# DisplayArrayPlus.net
KiCad netlist of a schematic drawn in EAGLE
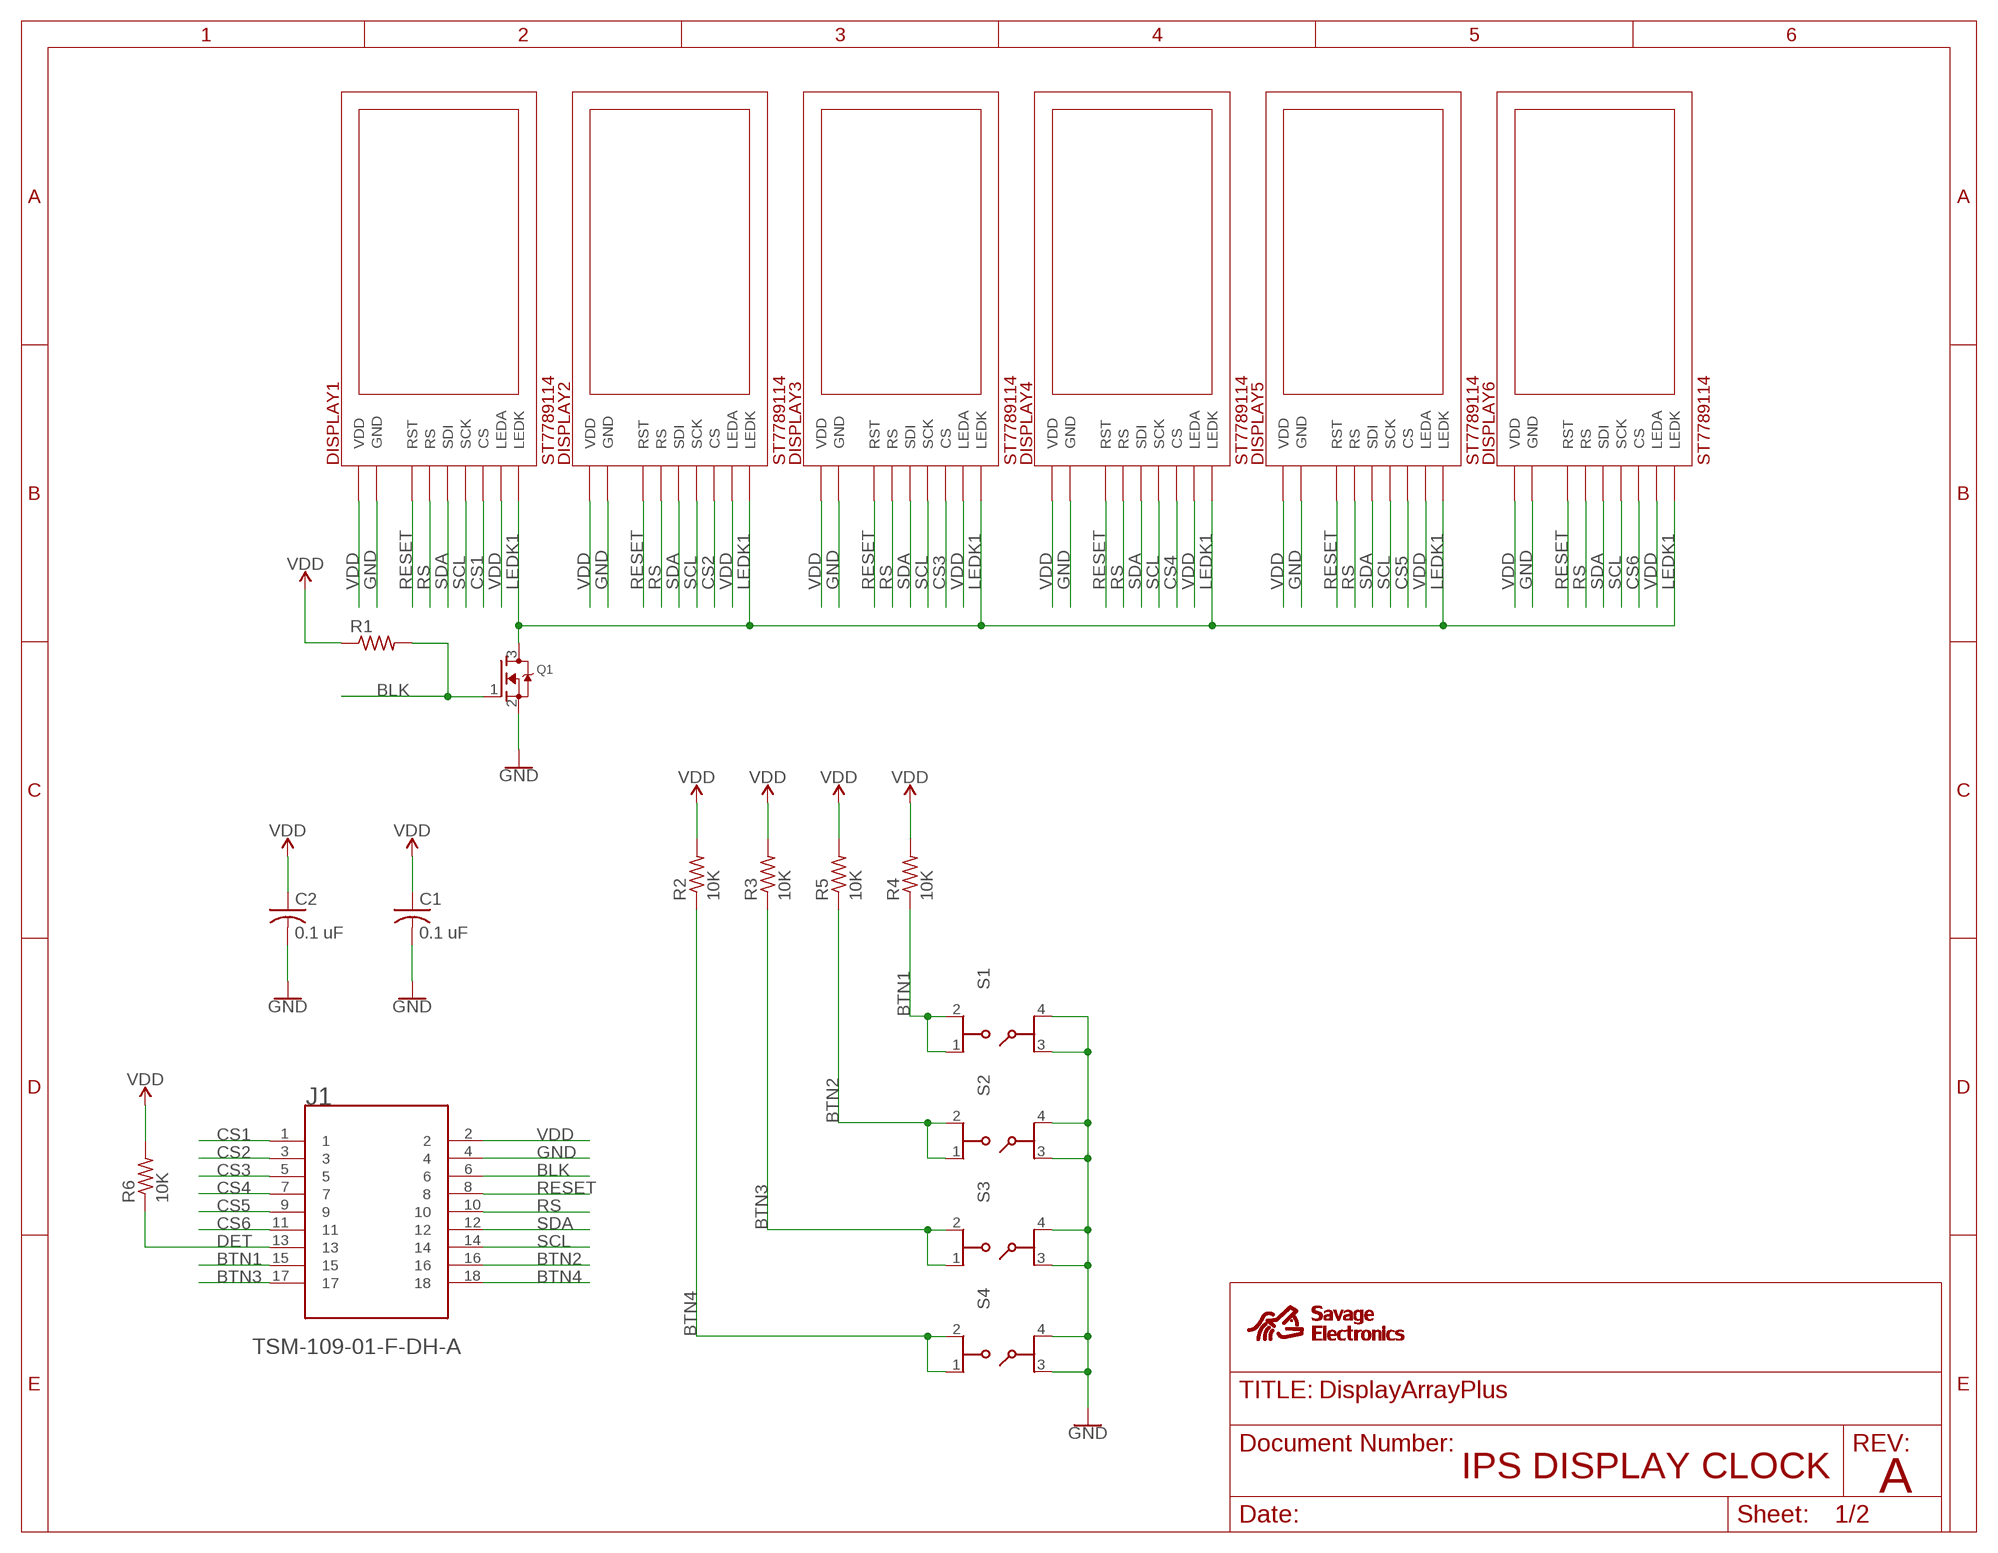
[diagram p0: schematic, sheet 1]

(export (version "E")
  (design (tool "Eeschema 10.0.6"))
  (components
    (comp (ref "C1")
      (value "0.1 uF")
      (footprint "eagle-import:C0603")
      (libsource (lib "eagle-import") (part "C-USC0603"))
    )
    (comp (ref "C2")
      (value "0.1 uF")
      (footprint "eagle-import:C0603")
      (libsource (lib "eagle-import") (part "C-USC0603"))
    )
    (comp (ref "DISPLAY1")
      (value "ST7789114")
      (footprint "eagle-import:IPSLCD114")
      (libsource (lib "eagle-import") (part "ST7789114"))
    )
    (comp (ref "DISPLAY2")
      (value "ST7789114")
      (footprint "eagle-import:IPSLCD114")
      (libsource (lib "eagle-import") (part "ST7789114"))
    )
    (comp (ref "DISPLAY3")
      (value "ST7789114")
      (footprint "eagle-import:IPSLCD114")
      (libsource (lib "eagle-import") (part "ST7789114"))
    )
    (comp (ref "DISPLAY4")
      (value "ST7789114")
      (footprint "eagle-import:IPSLCD114")
      (libsource (lib "eagle-import") (part "ST7789114"))
    )
    (comp (ref "DISPLAY5")
      (value "ST7789114")
      (footprint "eagle-import:IPSLCD114")
      (libsource (lib "eagle-import") (part "ST7789114"))
    )
    (comp (ref "DISPLAY6")
      (value "ST7789114")
      (footprint "eagle-import:IPSLCD114")
      (libsource (lib "eagle-import") (part "ST7789114"))
    )
    (comp (ref "J1")
      (value "TSM-109-01-F-DH-A")
      (footprint "eagle-import:SAMTEC-TSM-109-02-X-DH-A")
      (libsource (lib "eagle-import") (part "SAMTEC-TSM-109-02-X-DH-AJ"))
    )
    (comp (ref "Q1")
      (value "MOSFET-NREFLOW")
      (footprint "eagle-import:SOT23")
      (libsource (lib "eagle-import") (part "MOSFET-NREFLOW"))
    )
    (comp (ref "R1")
      (value "R-US_R0805")
      (footprint "eagle-import:R0805")
      (libsource (lib "eagle-import") (part "R-US_R0805"))
    )
    (comp (ref "R2")
      (value "10K")
      (footprint "eagle-import:R0805")
      (libsource (lib "eagle-import") (part "R-US_R0805"))
    )
    (comp (ref "R3")
      (value "10K")
      (footprint "eagle-import:R0805")
      (libsource (lib "eagle-import") (part "R-US_R0805"))
    )
    (comp (ref "R4")
      (value "10K")
      (footprint "eagle-import:R0805")
      (libsource (lib "eagle-import") (part "R-US_R0805"))
    )
    (comp (ref "R5")
      (value "10K")
      (footprint "eagle-import:R0805")
      (libsource (lib "eagle-import") (part "R-US_R0805"))
    )
    (comp (ref "R6")
      (value "10K")
      (footprint "eagle-import:R0805")
      (libsource (lib "eagle-import") (part "R-US_R0805"))
    )
    (comp (ref "S1")
      (value "434123025826")
      (footprint "eagle-import:434123025826")
      (libsource (lib "eagle-import") (part "434123025826"))
    )
    (comp (ref "S2")
      (value "434123025826")
      (footprint "eagle-import:434123025826")
      (libsource (lib "eagle-import") (part "434123025826"))
    )
    (comp (ref "S3")
      (value "434123025826")
      (footprint "eagle-import:434123025826")
      (libsource (lib "eagle-import") (part "434123025826"))
    )
    (comp (ref "S4")
      (value "434123025826")
      (footprint "eagle-import:434123025826")
      (libsource (lib "eagle-import") (part "434123025826"))
    )
    (comp (ref "U$3")
      (value "SE_SMALL_SILK")
      (footprint "eagle-import:SE_SMALL_SILK")
      (libsource (lib "eagle-import") (part "SE_SMALL_SILK"))
    )
  )
  (nets
    (net (code "1") (name "BLK") (class "Default")
      (node (ref "J1") (pin "6") (pinfunction "6_6") (pintype "passive"))
      (node (ref "Q1") (pin "1") (pinfunction "G_1") (pintype "bidirectional"))
      (node (ref "R1") (pin "2") (pinfunction "2_2") (pintype "passive"))
    )
    (net (code "2") (name "BTN1") (class "Default")
      (node (ref "J1") (pin "15") (pinfunction "15_15") (pintype "passive"))
      (node (ref "R4") (pin "1") (pinfunction "1_1") (pintype "passive"))
      (node (ref "S1") (pin "1") (pinfunction "1_1") (pintype "passive"))
      (node (ref "S1") (pin "2") (pinfunction "2_2") (pintype "passive"))
    )
    (net (code "3") (name "BTN2") (class "Default")
      (node (ref "J1") (pin "16") (pinfunction "16_16") (pintype "passive"))
      (node (ref "R5") (pin "1") (pinfunction "1_1") (pintype "passive"))
      (node (ref "S2") (pin "1") (pinfunction "1_1") (pintype "passive"))
      (node (ref "S2") (pin "2") (pinfunction "2_2") (pintype "passive"))
    )
    (net (code "4") (name "BTN3") (class "Default")
      (node (ref "J1") (pin "17") (pinfunction "17_17") (pintype "passive"))
      (node (ref "R3") (pin "1") (pinfunction "1_1") (pintype "passive"))
      (node (ref "S3") (pin "1") (pinfunction "1_1") (pintype "passive"))
      (node (ref "S3") (pin "2") (pinfunction "2_2") (pintype "passive"))
    )
    (net (code "5") (name "BTN4") (class "Default")
      (node (ref "J1") (pin "18") (pinfunction "18_18") (pintype "passive"))
      (node (ref "R2") (pin "1") (pinfunction "1_1") (pintype "passive"))
      (node (ref "S4") (pin "1") (pinfunction "1_1") (pintype "passive"))
      (node (ref "S4") (pin "2") (pinfunction "2_2") (pintype "passive"))
    )
    (net (code "6") (name "CS1") (class "Default")
      (node (ref "DISPLAY1") (pin "7") (pinfunction "CS_7") (pintype "bidirectional"))
      (node (ref "J1") (pin "1") (pinfunction "1_1") (pintype "passive"))
    )
    (net (code "7") (name "CS2") (class "Default")
      (node (ref "DISPLAY2") (pin "7") (pinfunction "CS_7") (pintype "bidirectional"))
      (node (ref "J1") (pin "3") (pinfunction "3_3") (pintype "passive"))
    )
    (net (code "8") (name "CS3") (class "Default")
      (node (ref "DISPLAY3") (pin "7") (pinfunction "CS_7") (pintype "bidirectional"))
      (node (ref "J1") (pin "5") (pinfunction "5_5") (pintype "passive"))
    )
    (net (code "9") (name "CS4") (class "Default")
      (node (ref "DISPLAY4") (pin "7") (pinfunction "CS_7") (pintype "bidirectional"))
      (node (ref "J1") (pin "7") (pinfunction "7_7") (pintype "passive"))
    )
    (net (code "10") (name "CS5") (class "Default")
      (node (ref "DISPLAY5") (pin "7") (pinfunction "CS_7") (pintype "bidirectional"))
      (node (ref "J1") (pin "9") (pinfunction "9_9") (pintype "passive"))
    )
    (net (code "11") (name "CS6") (class "Default")
      (node (ref "DISPLAY6") (pin "7") (pinfunction "CS_7") (pintype "bidirectional"))
      (node (ref "J1") (pin "11") (pinfunction "11_11") (pintype "passive"))
    )
    (net (code "12") (name "DET") (class "Default")
      (node (ref "J1") (pin "13") (pinfunction "13_13") (pintype "passive"))
      (node (ref "R6") (pin "1") (pinfunction "1_1") (pintype "passive"))
    )
    (net (code "13") (name "GND") (class "Default")
      (node (ref "C1") (pin "2") (pinfunction "2_2") (pintype "passive"))
      (node (ref "C2") (pin "2") (pinfunction "2_2") (pintype "passive"))
      (node (ref "DISPLAY1") (pin "13") (pinfunction "GND_13") (pintype "bidirectional"))
      (node (ref "DISPLAY1") (pin "8") (pinfunction "GND_8") (pintype "bidirectional"))
      (node (ref "DISPLAY2") (pin "13") (pinfunction "GND_13") (pintype "bidirectional"))
      (node (ref "DISPLAY2") (pin "8") (pinfunction "GND_8") (pintype "bidirectional"))
      (node (ref "DISPLAY3") (pin "13") (pinfunction "GND_13") (pintype "bidirectional"))
      (node (ref "DISPLAY3") (pin "8") (pinfunction "GND_8") (pintype "bidirectional"))
      (node (ref "DISPLAY4") (pin "13") (pinfunction "GND_13") (pintype "bidirectional"))
      (node (ref "DISPLAY4") (pin "8") (pinfunction "GND_8") (pintype "bidirectional"))
      (node (ref "DISPLAY5") (pin "13") (pinfunction "GND_13") (pintype "bidirectional"))
      (node (ref "DISPLAY5") (pin "8") (pinfunction "GND_8") (pintype "bidirectional"))
      (node (ref "DISPLAY6") (pin "13") (pinfunction "GND_13") (pintype "bidirectional"))
      (node (ref "DISPLAY6") (pin "8") (pinfunction "GND_8") (pintype "bidirectional"))
      (node (ref "J1") (pin "4") (pinfunction "4_4") (pintype "passive"))
      (node (ref "Q1") (pin "2") (pinfunction "S_2") (pintype "bidirectional"))
      (node (ref "S1") (pin "3") (pinfunction "3_3") (pintype "passive"))
      (node (ref "S1") (pin "4") (pinfunction "4_4") (pintype "passive"))
      (node (ref "S2") (pin "3") (pinfunction "3_3") (pintype "passive"))
      (node (ref "S2") (pin "4") (pinfunction "4_4") (pintype "passive"))
      (node (ref "S3") (pin "3") (pinfunction "3_3") (pintype "passive"))
      (node (ref "S3") (pin "4") (pinfunction "4_4") (pintype "passive"))
      (node (ref "S4") (pin "3") (pinfunction "3_3") (pintype "passive"))
      (node (ref "S4") (pin "4") (pinfunction "4_4") (pintype "passive"))
    )
    (net (code "14") (name "LEDK1") (class "Default")
      (node (ref "DISPLAY1") (pin "11") (pinfunction "LEDK_11") (pintype "bidirectional"))
      (node (ref "DISPLAY2") (pin "11") (pinfunction "LEDK_11") (pintype "bidirectional"))
      (node (ref "DISPLAY3") (pin "11") (pinfunction "LEDK_11") (pintype "bidirectional"))
      (node (ref "DISPLAY4") (pin "11") (pinfunction "LEDK_11") (pintype "bidirectional"))
      (node (ref "DISPLAY5") (pin "11") (pinfunction "LEDK_11") (pintype "bidirectional"))
      (node (ref "DISPLAY6") (pin "11") (pinfunction "LEDK_11") (pintype "bidirectional"))
      (node (ref "Q1") (pin "3") (pinfunction "D_3") (pintype "bidirectional"))
    )
    (net (code "15") (name "RESET") (class "Default")
      (node (ref "DISPLAY1") (pin "6") (pinfunction "RST_6") (pintype "bidirectional"))
      (node (ref "DISPLAY2") (pin "6") (pinfunction "RST_6") (pintype "bidirectional"))
      (node (ref "DISPLAY3") (pin "6") (pinfunction "RST_6") (pintype "bidirectional"))
      (node (ref "DISPLAY4") (pin "6") (pinfunction "RST_6") (pintype "bidirectional"))
      (node (ref "DISPLAY5") (pin "6") (pinfunction "RST_6") (pintype "bidirectional"))
      (node (ref "DISPLAY6") (pin "6") (pinfunction "RST_6") (pintype "bidirectional"))
      (node (ref "J1") (pin "8") (pinfunction "8_8") (pintype "passive"))
    )
    (net (code "16") (name "RS") (class "Default")
      (node (ref "DISPLAY1") (pin "5") (pinfunction "RS_5") (pintype "bidirectional"))
      (node (ref "DISPLAY2") (pin "5") (pinfunction "RS_5") (pintype "bidirectional"))
      (node (ref "DISPLAY3") (pin "5") (pinfunction "RS_5") (pintype "bidirectional"))
      (node (ref "DISPLAY4") (pin "5") (pinfunction "RS_5") (pintype "bidirectional"))
      (node (ref "DISPLAY5") (pin "5") (pinfunction "RS_5") (pintype "bidirectional"))
      (node (ref "DISPLAY6") (pin "5") (pinfunction "RS_5") (pintype "bidirectional"))
      (node (ref "J1") (pin "10") (pinfunction "10_10") (pintype "passive"))
    )
    (net (code "17") (name "SCL") (class "Default")
      (node (ref "DISPLAY1") (pin "4") (pinfunction "SCK_4") (pintype "bidirectional"))
      (node (ref "DISPLAY2") (pin "4") (pinfunction "SCK_4") (pintype "bidirectional"))
      (node (ref "DISPLAY3") (pin "4") (pinfunction "SCK_4") (pintype "bidirectional"))
      (node (ref "DISPLAY4") (pin "4") (pinfunction "SCK_4") (pintype "bidirectional"))
      (node (ref "DISPLAY5") (pin "4") (pinfunction "SCK_4") (pintype "bidirectional"))
      (node (ref "DISPLAY6") (pin "4") (pinfunction "SCK_4") (pintype "bidirectional"))
      (node (ref "J1") (pin "14") (pinfunction "14_14") (pintype "passive"))
    )
    (net (code "18") (name "SDA") (class "Default")
      (node (ref "DISPLAY1") (pin "3") (pinfunction "SDI_3") (pintype "bidirectional"))
      (node (ref "DISPLAY2") (pin "3") (pinfunction "SDI_3") (pintype "bidirectional"))
      (node (ref "DISPLAY3") (pin "3") (pinfunction "SDI_3") (pintype "bidirectional"))
      (node (ref "DISPLAY4") (pin "3") (pinfunction "SDI_3") (pintype "bidirectional"))
      (node (ref "DISPLAY5") (pin "3") (pinfunction "SDI_3") (pintype "bidirectional"))
      (node (ref "DISPLAY6") (pin "3") (pinfunction "SDI_3") (pintype "bidirectional"))
      (node (ref "J1") (pin "12") (pinfunction "12_12") (pintype "passive"))
    )
    (net (code "19") (name "VDD") (class "Default")
      (node (ref "C1") (pin "1") (pinfunction "1_1") (pintype "passive"))
      (node (ref "C2") (pin "1") (pinfunction "1_1") (pintype "passive"))
      (node (ref "DISPLAY1") (pin "10") (pinfunction "VDD_10") (pintype "bidirectional"))
      (node (ref "DISPLAY1") (pin "12") (pinfunction "LEDA_12") (pintype "bidirectional"))
      (node (ref "DISPLAY2") (pin "10") (pinfunction "VDD_10") (pintype "bidirectional"))
      (node (ref "DISPLAY2") (pin "12") (pinfunction "LEDA_12") (pintype "bidirectional"))
      (node (ref "DISPLAY3") (pin "10") (pinfunction "VDD_10") (pintype "bidirectional"))
      (node (ref "DISPLAY3") (pin "12") (pinfunction "LEDA_12") (pintype "bidirectional"))
      (node (ref "DISPLAY4") (pin "10") (pinfunction "VDD_10") (pintype "bidirectional"))
      (node (ref "DISPLAY4") (pin "12") (pinfunction "LEDA_12") (pintype "bidirectional"))
      (node (ref "DISPLAY5") (pin "10") (pinfunction "VDD_10") (pintype "bidirectional"))
      (node (ref "DISPLAY5") (pin "12") (pinfunction "LEDA_12") (pintype "bidirectional"))
      (node (ref "DISPLAY6") (pin "10") (pinfunction "VDD_10") (pintype "bidirectional"))
      (node (ref "DISPLAY6") (pin "12") (pinfunction "LEDA_12") (pintype "bidirectional"))
      (node (ref "J1") (pin "2") (pinfunction "2_2") (pintype "passive"))
      (node (ref "R1") (pin "1") (pinfunction "1_1") (pintype "passive"))
      (node (ref "R2") (pin "2") (pinfunction "2_2") (pintype "passive"))
      (node (ref "R3") (pin "2") (pinfunction "2_2") (pintype "passive"))
      (node (ref "R4") (pin "2") (pinfunction "2_2") (pintype "passive"))
      (node (ref "R5") (pin "2") (pinfunction "2_2") (pintype "passive"))
      (node (ref "R6") (pin "2") (pinfunction "2_2") (pintype "passive"))
    )
  )
)
